# PIC32_dev.net
KiCad netlist of a schematic drawn in EAGLE
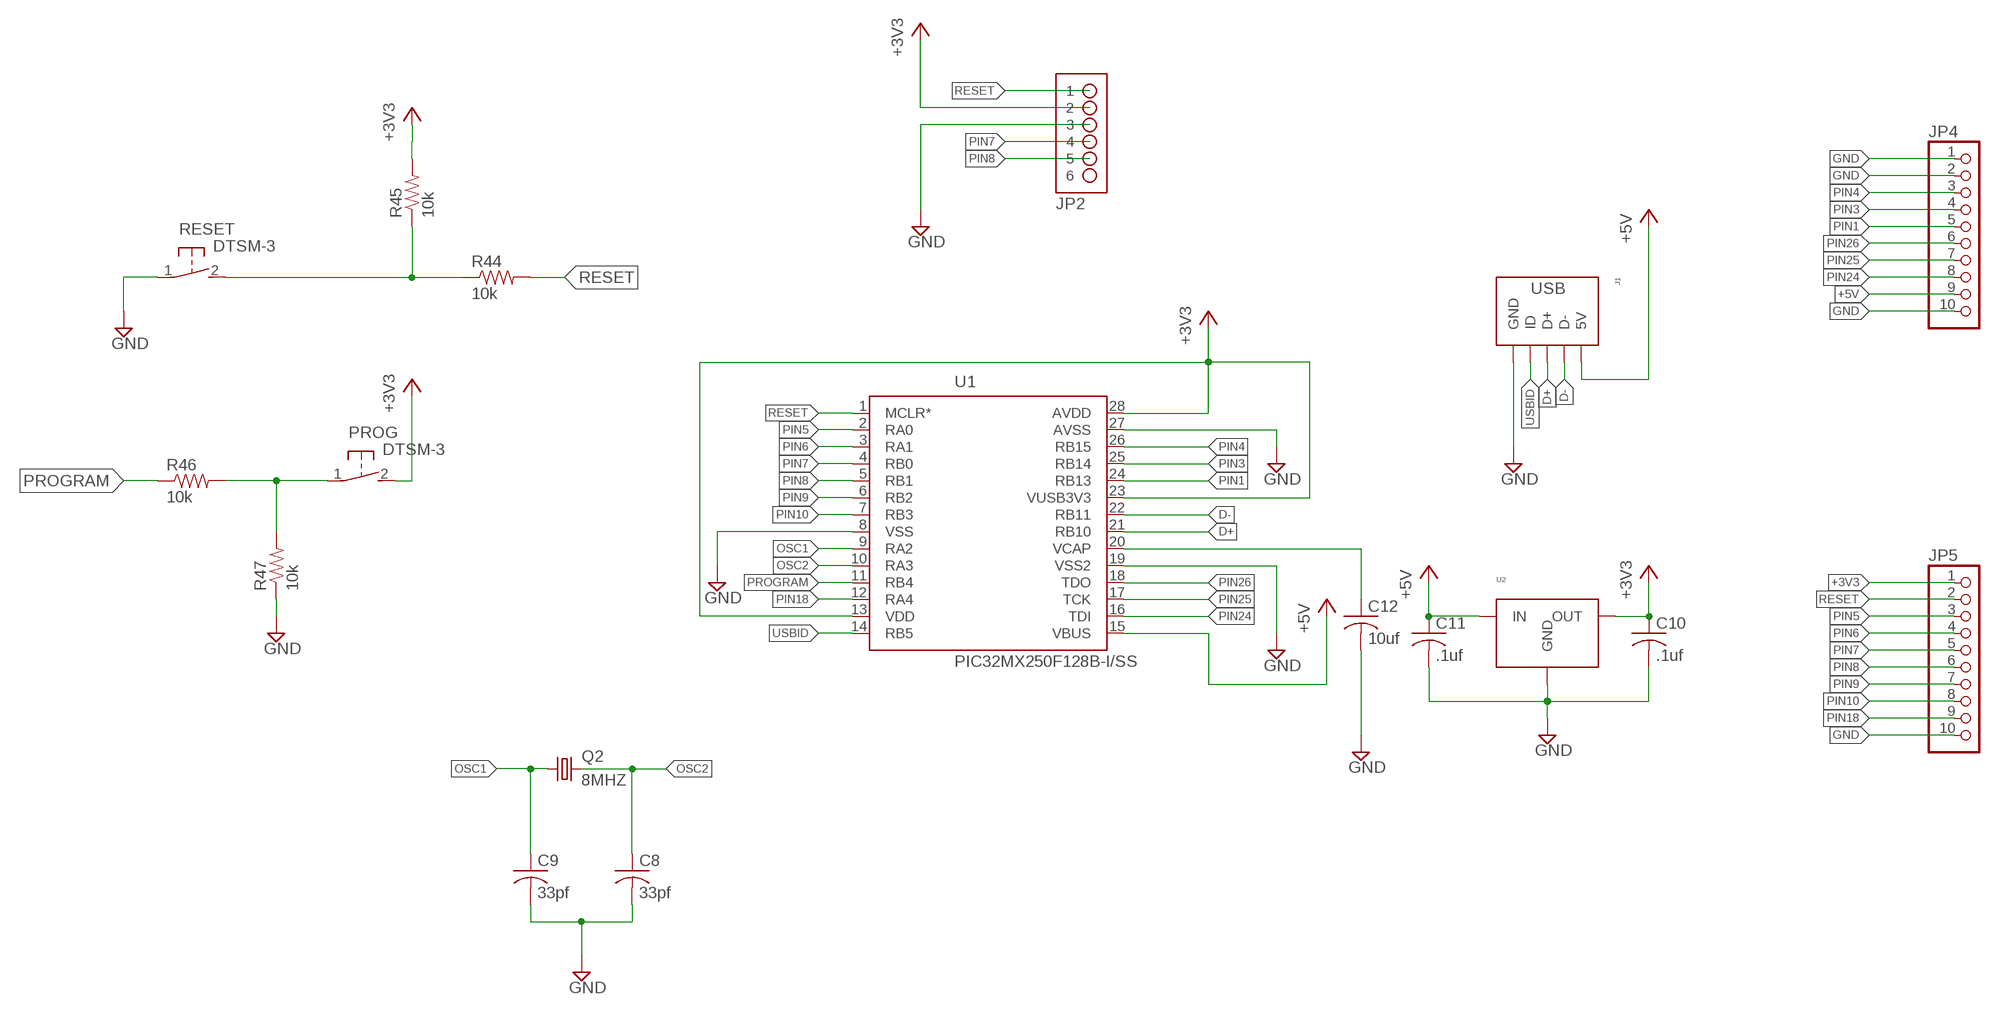
[diagram p0: schematic, sheet 1]

(export (version "E")
  (design (tool "Eeschema 10.0.6"))
  (components
    (comp (ref "C8")
      (value "33pf")
      (footprint "eagle-import:C1206")
      (libsource (lib "eagle-import") (part "resistor_C-USC1206"))
    )
    (comp (ref "C9")
      (value "33pf")
      (footprint "eagle-import:C1206")
      (libsource (lib "eagle-import") (part "resistor_C-USC1206"))
    )
    (comp (ref "C10")
      (value ".1uf")
      (footprint "eagle-import:C1206")
      (libsource (lib "eagle-import") (part "resistor_C-USC1206"))
    )
    (comp (ref "C11")
      (value ".1uf")
      (footprint "eagle-import:C1206")
      (libsource (lib "eagle-import") (part "resistor_C-USC1206"))
    )
    (comp (ref "C12")
      (value "10uf")
      (footprint "eagle-import:C1206")
      (libsource (lib "eagle-import") (part "C-USC1206"))
    )
    (comp (ref "J1")
      (value "USBMC32599")
      (footprint "eagle-import:MC32599")
      (libsource (lib "eagle-import") (part "USBMC32599"))
    )
    (comp (ref "JP2")
      (value "HDR-1X6-OFFSET")
      (footprint "eagle-import:HDR-1X6_OFFSET")
      (libsource (lib "eagle-import") (part "HDR-1X6-OFFSET"))
    )
    (comp (ref "JP4")
      (value "PINHD-1X10")
      (footprint "eagle-import:1X10")
      (libsource (lib "eagle-import") (part "PINHD-1X10"))
    )
    (comp (ref "JP5")
      (value "PINHD-1X10")
      (footprint "eagle-import:1X10")
      (libsource (lib "eagle-import") (part "PINHD-1X10"))
    )
    (comp (ref "PROG")
      (value "DTSM-3")
      (footprint "eagle-import:DTSM-3")
      (libsource (lib "eagle-import") (part "DTSM-3"))
    )
    (comp (ref "Q2")
      (value "8MHZ")
      (footprint "eagle-import:CTS406")
      (libsource (lib "eagle-import") (part "CRYSTALCTS406"))
    )
    (comp (ref "R44")
      (value "10k")
      (footprint "eagle-import:1206")
      (libsource (lib "eagle-import") (part "RESISTOR1206"))
    )
    (comp (ref "R45")
      (value "10k")
      (footprint "eagle-import:1206")
      (libsource (lib "eagle-import") (part "RESISTOR1206"))
    )
    (comp (ref "R46")
      (value "10k")
      (footprint "eagle-import:1206")
      (libsource (lib "eagle-import") (part "RESISTOR1206"))
    )
    (comp (ref "R47")
      (value "10k")
      (footprint "eagle-import:1206")
      (libsource (lib "eagle-import") (part "RESISTOR1206"))
    )
    (comp (ref "RESET")
      (value "DTSM-3")
      (footprint "eagle-import:DTSM-3")
      (libsource (lib "eagle-import") (part "DTSM-3"))
    )
    (comp (ref "U1")
      (value "PIC32MX250F128B-I/SS")
      (footprint "eagle-import:SOP65P780X200-28N")
      (fields (field (name "MPN") "PIC32MX250F128B-I/SS "))
      (libsource (lib "eagle-import") (part "PIC32MX2/SS50F128B-I"))
    )
    (comp (ref "U2")
      (value "FIXED_VOLTAGE_REGDPAK-3")
      (footprint "eagle-import:DPAK-3")
      (libsource (lib "eagle-import") (part "FIXED_VOLTAGE_REGDPAK-3"))
    )
  )
  (nets
    (net (code "1") (name "+3V3") (class "Default")
      (node (ref "C10") (pin "1") (pinfunction "1_1") (pintype "passive"))
      (node (ref "JP2") (pin "2") (pinfunction "2_2") (pintype "passive"))
      (node (ref "JP5") (pin "1") (pinfunction "1_1") (pintype "passive"))
      (node (ref "PROG") (pin "2") (pinfunction "2_2") (pintype "passive"))
      (node (ref "R45") (pin "2") (pinfunction "2_2") (pintype "passive"))
      (node (ref "U1") (pin "13") (pinfunction "VDD_13") (pintype "power_in"))
      (node (ref "U1") (pin "23") (pinfunction "VUSB3V3_23") (pintype "passive"))
      (node (ref "U1") (pin "28") (pinfunction "AVDD_28") (pintype "power_in"))
      (node (ref "U2") (pin "2") (pinfunction "OUT_2") (pintype "bidirectional"))
    )
    (net (code "2") (name "+5V") (class "Default")
      (node (ref "C11") (pin "1") (pinfunction "1_1") (pintype "passive"))
      (node (ref "J1") (pin "V_BUS") (pinfunction "5V_V_BUS") (pintype "bidirectional"))
      (node (ref "JP4") (pin "9") (pinfunction "9_9") (pintype "passive"))
      (node (ref "U1") (pin "15") (pinfunction "VBUS_15") (pintype "passive"))
      (node (ref "U2") (pin "1") (pinfunction "IN_1") (pintype "bidirectional"))
    )
    (net (code "3") (name "D+") (class "Default")
      (node (ref "J1") (pin "D+") (pinfunction "D+_D+") (pintype "bidirectional"))
      (node (ref "U1") (pin "21") (pinfunction "RB10_21") (pintype "bidirectional"))
    )
    (net (code "4") (name "D-") (class "Default")
      (node (ref "J1") (pin "D-") (pinfunction "D-_D-") (pintype "bidirectional"))
      (node (ref "U1") (pin "22") (pinfunction "RB11_22") (pintype "bidirectional"))
    )
    (net (code "5") (name "GND") (class "Default")
      (node (ref "C10") (pin "2") (pinfunction "2_2") (pintype "passive"))
      (node (ref "C11") (pin "2") (pinfunction "2_2") (pintype "passive"))
      (node (ref "C12") (pin "2") (pinfunction "2_2") (pintype "passive"))
      (node (ref "C8") (pin "2") (pinfunction "2_2") (pintype "passive"))
      (node (ref "C9") (pin "2") (pinfunction "2_2") (pintype "passive"))
      (node (ref "J1") (pin "GND") (pinfunction "GND_GND") (pintype "bidirectional"))
      (node (ref "J1") (pin "SH_0") (pinfunction "GND_SH_0") (pintype "bidirectional"))
      (node (ref "J1") (pin "SH_1") (pinfunction "GND_SH_1") (pintype "bidirectional"))
      (node (ref "J1") (pin "SH_2") (pinfunction "GND_SH_2") (pintype "bidirectional"))
      (node (ref "J1") (pin "SH_3") (pinfunction "GND_SH_3") (pintype "bidirectional"))
      (node (ref "JP2") (pin "3") (pinfunction "3_3") (pintype "passive"))
      (node (ref "JP4") (pin "1") (pinfunction "1_1") (pintype "passive"))
      (node (ref "JP4") (pin "10") (pinfunction "10_10") (pintype "passive"))
      (node (ref "JP4") (pin "2") (pinfunction "2_2") (pintype "passive"))
      (node (ref "JP5") (pin "10") (pinfunction "10_10") (pintype "passive"))
      (node (ref "R47") (pin "1") (pinfunction "1_1") (pintype "passive"))
      (node (ref "RESET") (pin "1") (pinfunction "1_1") (pintype "passive"))
      (node (ref "U1") (pin "19") (pinfunction "VSS2_19") (pintype "power_in"))
      (node (ref "U1") (pin "27") (pinfunction "AVSS_27") (pintype "power_in"))
      (node (ref "U1") (pin "8") (pinfunction "VSS_8") (pintype "power_in"))
      (node (ref "U2") (pin "4") (pinfunction "GND_4") (pintype "bidirectional"))
    )
    (net (code "6") (name "Net-(PROG-Pad1)") (class "Default")
      (node (ref "PROG") (pin "1") (pinfunction "1_1") (pintype "passive"))
      (node (ref "R46") (pin "2") (pinfunction "2_2") (pintype "passive"))
      (node (ref "R47") (pin "2") (pinfunction "2_2") (pintype "passive"))
    )
    (net (code "7") (name "Net-(R44-Pad1)") (class "Default")
      (node (ref "R44") (pin "1") (pinfunction "1_1") (pintype "passive"))
      (node (ref "R45") (pin "1") (pinfunction "1_1") (pintype "passive"))
      (node (ref "RESET") (pin "2") (pinfunction "2_2") (pintype "passive"))
    )
    (net (code "8") (name "Net-(U1-VCAP)") (class "Default")
      (node (ref "C12") (pin "1") (pinfunction "1_1") (pintype "passive"))
      (node (ref "U1") (pin "20") (pinfunction "VCAP_20") (pintype "power_in"))
    )
    (net (code "9") (name "OSC1") (class "Default")
      (node (ref "C9") (pin "1") (pinfunction "1_1") (pintype "passive"))
      (node (ref "Q2") (pin "1") (pinfunction "1_1") (pintype "passive"))
      (node (ref "U1") (pin "9") (pinfunction "RA2_9") (pintype "bidirectional"))
    )
    (net (code "10") (name "OSC2") (class "Default")
      (node (ref "C8") (pin "1") (pinfunction "1_1") (pintype "passive"))
      (node (ref "Q2") (pin "3") (pinfunction "2_3") (pintype "passive"))
      (node (ref "U1") (pin "10") (pinfunction "RA3_10") (pintype "bidirectional"))
    )
    (net (code "11") (name "PIN1") (class "Default")
      (node (ref "JP4") (pin "5") (pinfunction "5_5") (pintype "passive"))
      (node (ref "U1") (pin "24") (pinfunction "RB13_24") (pintype "bidirectional"))
    )
    (net (code "12") (name "PIN3") (class "Default")
      (node (ref "JP4") (pin "4") (pinfunction "4_4") (pintype "passive"))
      (node (ref "U1") (pin "25") (pinfunction "RB14_25") (pintype "bidirectional"))
    )
    (net (code "13") (name "PIN4") (class "Default")
      (node (ref "JP4") (pin "3") (pinfunction "3_3") (pintype "passive"))
      (node (ref "U1") (pin "26") (pinfunction "RB15_26") (pintype "bidirectional"))
    )
    (net (code "14") (name "PIN5") (class "Default")
      (node (ref "JP5") (pin "3") (pinfunction "3_3") (pintype "passive"))
      (node (ref "U1") (pin "2") (pinfunction "RA0_2") (pintype "bidirectional"))
    )
    (net (code "15") (name "PIN6") (class "Default")
      (node (ref "JP5") (pin "4") (pinfunction "4_4") (pintype "passive"))
      (node (ref "U1") (pin "3") (pinfunction "RA1_3") (pintype "bidirectional"))
    )
    (net (code "16") (name "PIN7") (class "Default")
      (node (ref "JP2") (pin "4") (pinfunction "4_4") (pintype "passive"))
      (node (ref "JP5") (pin "5") (pinfunction "5_5") (pintype "passive"))
      (node (ref "U1") (pin "4") (pinfunction "RB0_4") (pintype "bidirectional"))
    )
    (net (code "17") (name "PIN8") (class "Default")
      (node (ref "JP2") (pin "5") (pinfunction "5_5") (pintype "passive"))
      (node (ref "JP5") (pin "6") (pinfunction "6_6") (pintype "passive"))
      (node (ref "U1") (pin "5") (pinfunction "RB1_5") (pintype "bidirectional"))
    )
    (net (code "18") (name "PIN9") (class "Default")
      (node (ref "JP5") (pin "7") (pinfunction "7_7") (pintype "passive"))
      (node (ref "U1") (pin "6") (pinfunction "RB2_6") (pintype "bidirectional"))
    )
    (net (code "19") (name "PIN10") (class "Default")
      (node (ref "JP5") (pin "8") (pinfunction "8_8") (pintype "passive"))
      (node (ref "U1") (pin "7") (pinfunction "RB3_7") (pintype "bidirectional"))
    )
    (net (code "20") (name "PIN18") (class "Default")
      (node (ref "JP5") (pin "9") (pinfunction "9_9") (pintype "passive"))
      (node (ref "U1") (pin "12") (pinfunction "RA4_12") (pintype "bidirectional"))
    )
    (net (code "21") (name "PIN24") (class "Default")
      (node (ref "JP4") (pin "8") (pinfunction "8_8") (pintype "passive"))
      (node (ref "U1") (pin "16") (pinfunction "TDI_16") (pintype "input"))
    )
    (net (code "22") (name "PIN25") (class "Default")
      (node (ref "JP4") (pin "7") (pinfunction "7_7") (pintype "passive"))
      (node (ref "U1") (pin "17") (pinfunction "TCK_17") (pintype "input"))
    )
    (net (code "23") (name "PIN26") (class "Default")
      (node (ref "JP4") (pin "6") (pinfunction "6_6") (pintype "passive"))
      (node (ref "U1") (pin "18") (pinfunction "TDO_18") (pintype "output"))
    )
    (net (code "24") (name "PROGRAM") (class "Default")
      (node (ref "R46") (pin "1") (pinfunction "1_1") (pintype "passive"))
      (node (ref "U1") (pin "11") (pinfunction "RB4_11") (pintype "bidirectional"))
    )
    (net (code "25") (name "RESET") (class "Default")
      (node (ref "JP2") (pin "1") (pinfunction "1_1") (pintype "passive"))
      (node (ref "JP5") (pin "2") (pinfunction "2_2") (pintype "passive"))
      (node (ref "R44") (pin "2") (pinfunction "2_2") (pintype "passive"))
      (node (ref "U1") (pin "1") (pinfunction "MCLR*_1") (pintype "input"))
    )
    (net (code "26") (name "USBID") (class "Default")
      (node (ref "J1") (pin "N/C") (pinfunction "ID_N/C") (pintype "bidirectional"))
      (node (ref "U1") (pin "14") (pinfunction "RB5_14") (pintype "bidirectional"))
    )
    (net (code "27") (name "unconnected-(JP2-Pad6)") (class "Default")
      (node (ref "JP2") (pin "6") (pinfunction "6_6") (pintype "passive"))
    )
  )
)
